# 08_-_PERIPHERALS_A.net
KiCad netlist of a schematic drawn in Altium Designer
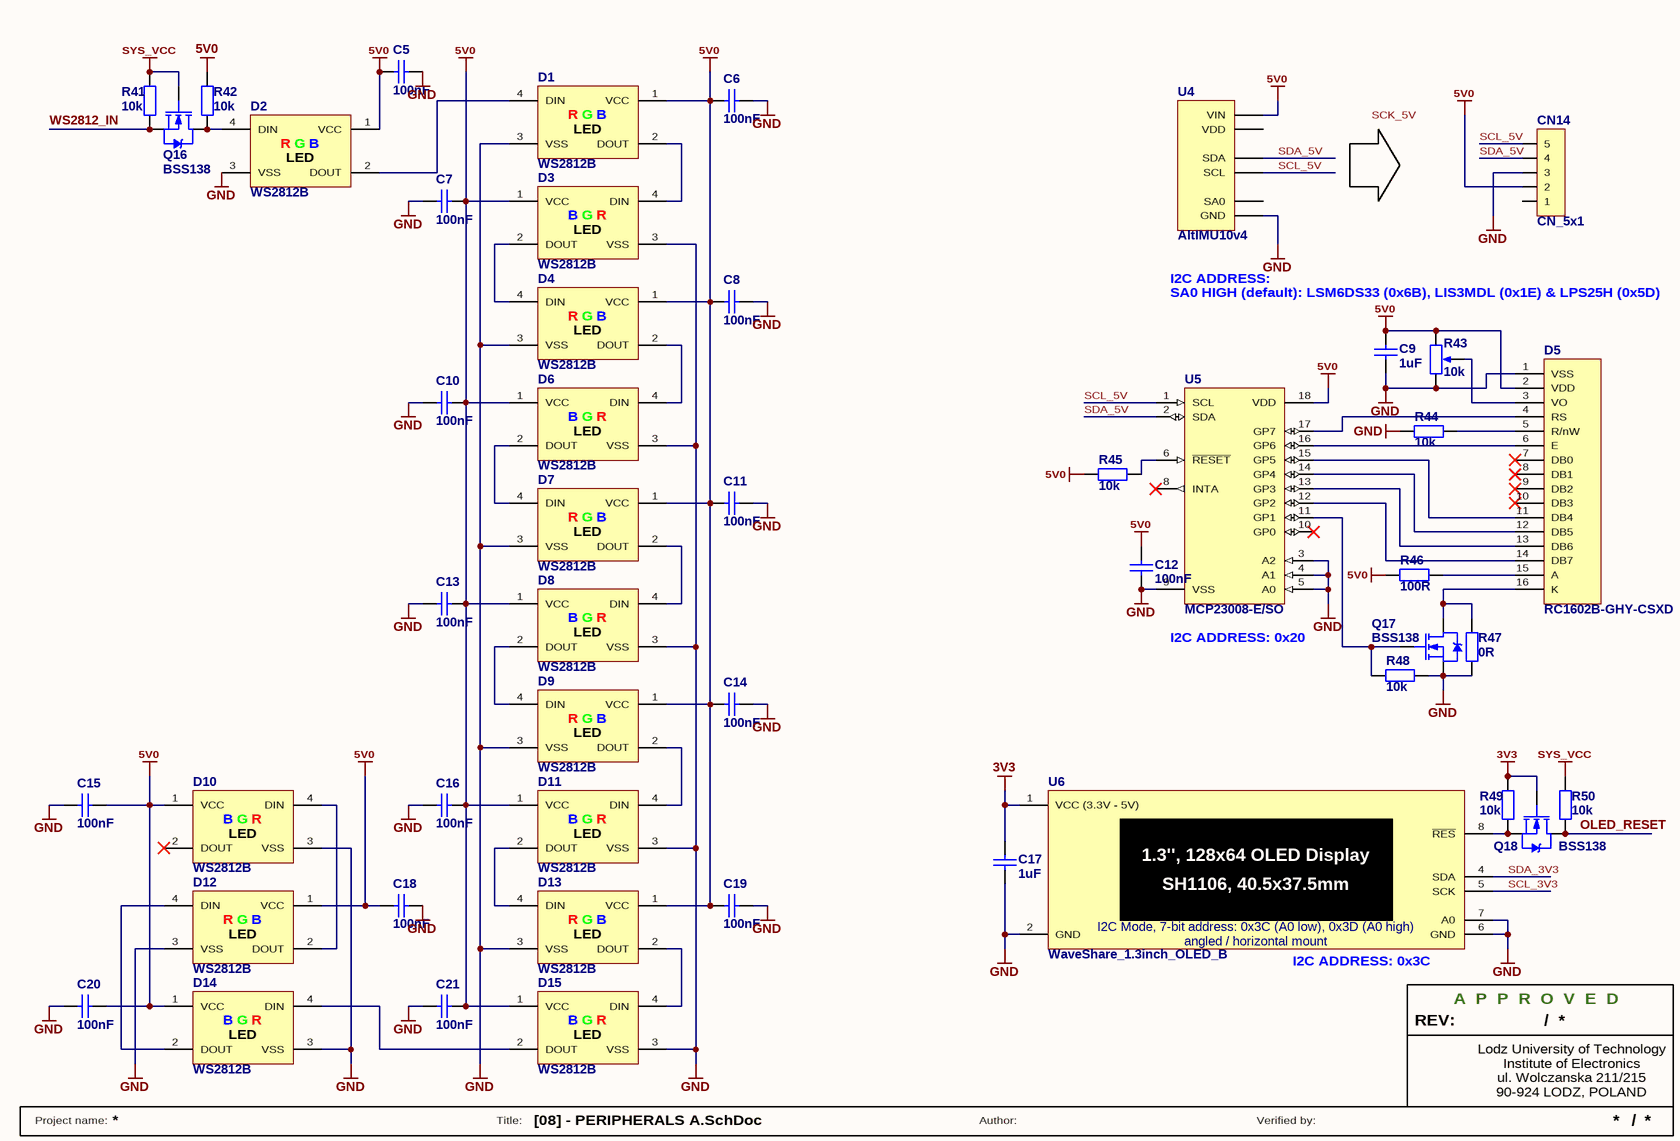
[diagram p0: [08] - PERIPHERALS A.SchDoc]

(export (version "E")
  (design (tool "Eeschema 10.0.6"))
  (components
    (comp (ref "C5")
      (value "100nF")
      (footprint "C0805")
      (description "Capacitor")
      (libsource (lib "capacitors") (part "Cap"))
    )
    (comp (ref "C6")
      (value "100nF")
      (footprint "C0805")
      (description "Capacitor")
      (libsource (lib "capacitors") (part "Cap"))
    )
    (comp (ref "C7")
      (value "100nF")
      (footprint "C0805")
      (description "Capacitor")
      (libsource (lib "capacitors") (part "Cap"))
    )
    (comp (ref "C8")
      (value "100nF")
      (footprint "C0805")
      (description "Capacitor")
      (libsource (lib "capacitors") (part "Cap"))
    )
    (comp (ref "C9")
      (value "1uF")
      (footprint "C0805")
      (description "Capacitor")
      (libsource (lib "capacitors") (part "Cap"))
    )
    (comp (ref "C10")
      (value "100nF")
      (footprint "C0805")
      (description "Capacitor")
      (libsource (lib "capacitors") (part "Cap"))
    )
    (comp (ref "C11")
      (value "100nF")
      (footprint "C0805")
      (description "Capacitor")
      (libsource (lib "capacitors") (part "Cap"))
    )
    (comp (ref "C12")
      (value "100nF")
      (footprint "C0805")
      (description "Capacitor")
      (libsource (lib "capacitors") (part "Cap"))
    )
    (comp (ref "C13")
      (value "100nF")
      (footprint "C0805")
      (description "Capacitor")
      (libsource (lib "capacitors") (part "Cap"))
    )
    (comp (ref "C14")
      (value "100nF")
      (footprint "C0805")
      (description "Capacitor")
      (libsource (lib "capacitors") (part "Cap"))
    )
    (comp (ref "C15")
      (value "100nF")
      (footprint "C0805")
      (description "Capacitor")
      (libsource (lib "capacitors") (part "Cap"))
    )
    (comp (ref "C16")
      (value "100nF")
      (footprint "C0805")
      (description "Capacitor")
      (libsource (lib "capacitors") (part "Cap"))
    )
    (comp (ref "C17")
      (value "1uF")
      (footprint "C0805")
      (description "Capacitor")
      (libsource (lib "capacitors") (part "Cap"))
    )
    (comp (ref "C18")
      (value "100nF")
      (footprint "C0805")
      (description "Capacitor")
      (libsource (lib "capacitors") (part "Cap"))
    )
    (comp (ref "C19")
      (value "100nF")
      (footprint "C0805")
      (description "Capacitor")
      (libsource (lib "capacitors") (part "Cap"))
    )
    (comp (ref "C20")
      (value "100nF")
      (footprint "C0805")
      (description "Capacitor")
      (libsource (lib "capacitors") (part "Cap"))
    )
    (comp (ref "C21")
      (value "100nF")
      (footprint "C0805")
      (description "Capacitor")
      (libsource (lib "capacitors") (part "Cap"))
    )
    (comp (ref "CN14")
      (value "CN_5x1")
      (footprint "GP_5x1H_F")
      (libsource (lib "goldpin_female") (part "CN_5x1"))
    )
    (comp (ref "D1")
      (value "WS2812B")
      (footprint "WS2812B")
      (description "Intelligent control LED integrated light source")
      (libsource (lib "") (part "WS2812B_1"))
    )
    (comp (ref "D2")
      (value "WS2812B")
      (footprint "WS2812B")
      (description "Intelligent control LED integrated light source")
      (libsource (lib "") (part "WS2812B_1"))
    )
    (comp (ref "D3")
      (value "WS2812B")
      (footprint "WS2812B")
      (description "Intelligent control LED integrated light source")
      (libsource (lib "leds") (part "WS2812B"))
    )
    (comp (ref "D4")
      (value "WS2812B")
      (footprint "WS2812B")
      (description "Intelligent control LED integrated light source")
      (libsource (lib "") (part "WS2812B_1"))
    )
    (comp (ref "D5")
      (value "RC1602B-GHY-CSXD")
      (footprint "RC1602B-GHY-CSXD")
      (description "16x2 LCD Display")
      (libsource (lib "lcd_displays") (part "RC1602B-GHY-CSXD"))
    )
    (comp (ref "D6")
      (value "WS2812B")
      (footprint "WS2812B")
      (description "Intelligent control LED integrated light source")
      (libsource (lib "leds") (part "WS2812B"))
    )
    (comp (ref "D7")
      (value "WS2812B")
      (footprint "WS2812B")
      (description "Intelligent control LED integrated light source")
      (libsource (lib "") (part "WS2812B_1"))
    )
    (comp (ref "D8")
      (value "WS2812B")
      (footprint "WS2812B")
      (description "Intelligent control LED integrated light source")
      (libsource (lib "leds") (part "WS2812B"))
    )
    (comp (ref "D9")
      (value "WS2812B")
      (footprint "WS2812B")
      (description "Intelligent control LED integrated light source")
      (libsource (lib "") (part "WS2812B_1"))
    )
    (comp (ref "D10")
      (value "WS2812B")
      (footprint "WS2812B")
      (description "Intelligent control LED integrated light source")
      (libsource (lib "leds") (part "WS2812B"))
    )
    (comp (ref "D11")
      (value "WS2812B")
      (footprint "WS2812B")
      (description "Intelligent control LED integrated light source")
      (libsource (lib "leds") (part "WS2812B"))
    )
    (comp (ref "D12")
      (value "WS2812B")
      (footprint "WS2812B")
      (description "Intelligent control LED integrated light source")
      (libsource (lib "") (part "WS2812B_1"))
    )
    (comp (ref "D13")
      (value "WS2812B")
      (footprint "WS2812B")
      (description "Intelligent control LED integrated light source")
      (libsource (lib "") (part "WS2812B_1"))
    )
    (comp (ref "D14")
      (value "WS2812B")
      (footprint "WS2812B")
      (description "Intelligent control LED integrated light source")
      (libsource (lib "leds") (part "WS2812B"))
    )
    (comp (ref "D15")
      (value "WS2812B")
      (footprint "WS2812B")
      (description "Intelligent control LED integrated light source")
      (libsource (lib "leds") (part "WS2812B"))
    )
    (comp (ref "Q16")
      (value "BSS138")
      (footprint "SOT-23")
      (description "N-Channel Enhancement Mode Vertical DMOS FET")
      (fields (field (name "PUBLISHER") "Altium Limited"))
      (libsource (lib "transistors_other") (part "BSS138"))
    )
    (comp (ref "Q17")
      (value "BSS138")
      (footprint "SOT-23")
      (description "N-Channel Enhancement Mode Vertical DMOS FET")
      (fields (field (name "PUBLISHER") "Altium Limited"))
      (libsource (lib "transistors_other") (part "BSS138"))
    )
    (comp (ref "Q18")
      (value "BSS138")
      (footprint "SOT-23")
      (description "N-Channel Enhancement Mode Vertical DMOS FET")
      (fields (field (name "PUBLISHER") "Altium Limited"))
      (libsource (lib "transistors_other") (part "BSS138"))
    )
    (comp (ref "R41")
      (value "10k")
      (footprint "R0805")
      (description "Resistor")
      (libsource (lib "") (part "Res_1"))
    )
    (comp (ref "R42")
      (value "10k")
      (footprint "R0805")
      (description "Resistor")
      (libsource (lib "") (part "Res_1"))
    )
    (comp (ref "R43")
      (value "10k")
      (footprint "3305SMD")
      (description "3305SMD-10K")
      (libsource (lib "resistors") (part "3305SMD-10K"))
    )
    (comp (ref "R44")
      (value "10k")
      (footprint "R0805")
      (description "Resistor")
      (libsource (lib "resistors") (part "Res"))
    )
    (comp (ref "R45")
      (value "10k")
      (footprint "R0805")
      (description "Resistor")
      (libsource (lib "resistors") (part "Res"))
    )
    (comp (ref "R46")
      (value "100R")
      (footprint "R0805")
      (description "Resistor")
      (libsource (lib "resistors") (part "Res"))
    )
    (comp (ref "R47")
      (value "0R")
      (footprint "R0805")
      (description "Resistor")
      (libsource (lib "") (part "Res_2"))
    )
    (comp (ref "R48")
      (value "10k")
      (footprint "R0805")
      (description "Resistor")
      (libsource (lib "resistors") (part "Res"))
    )
    (comp (ref "R49")
      (value "10k")
      (footprint "R0805")
      (description "Resistor")
      (libsource (lib "") (part "Res_1"))
    )
    (comp (ref "R50")
      (value "10k")
      (footprint "R0805")
      (description "Resistor")
      (libsource (lib "") (part "Res_1"))
    )
    (comp (ref "U4")
      (value "AltIMU10v4")
      (footprint "AltIMU-10 v4_REVERSE")
      (description "Pololu Gyro, Accelerometer, Compass, and Altimeter (L3GD20H, LSM303D, and LPS25H Carrier)")
      (libsource (lib "mems_and_imu_modules") (part "AltIMU10v4"))
    )
    (comp (ref "U5")
      (value "MCP23008-E/SO")
      (footprint "SO18W")
      (description "8-Bit I/O Expander with Serial Interface I2C, 18-Pin SOIC Package")
      (libsource (lib "io_expanders") (part "MCP23008-E/SO"))
    )
    (comp (ref "U6")
      (value "WaveShare_1.3inch_OLED_B")
      (footprint "WaveShare_1.3INCH_OLED")
      (description "DEP096032B-W OLED Display")
      (libsource (lib "oled_displays") (part "WaveShare_1.3inch_OLED"))
    )
  )
  (nets
    (net (code "1") (name "/OLED_RESET") (class "Default")
      (node (ref "Q18") (pin "3") (pinfunction "D_3") (pintype "passive"))
      (node (ref "R50") (pin "1") (pinfunction "1_1") (pintype "passive"))
    )
    (net (code "3") (name "/SCL_3V3") (class "Default")
      (node (ref "U6") (pin "5") (pinfunction "SCK_5") (pintype "passive"))
    )
    (net (code "4") (name "/SCL_5V") (class "Default")
      (node (ref "CN14") (pin "5") (pinfunction "5_5") (pintype "passive"))
      (node (ref "U4") (pin "6") (pinfunction "SCL_6") (pintype "passive"))
      (node (ref "U5") (pin "1") (pinfunction "SCL_1") (pintype "input"))
    )
    (net (code "5") (name "/SDA_3V3") (class "Default")
      (node (ref "U6") (pin "4") (pinfunction "SDA_4") (pintype "passive"))
    )
    (net (code "6") (name "/SDA_5V") (class "Default")
      (node (ref "CN14") (pin "4") (pinfunction "4_4") (pintype "passive"))
      (node (ref "U4") (pin "5") (pinfunction "SDA_5") (pintype "passive"))
      (node (ref "U5") (pin "2") (pinfunction "SDA_2") (pintype "bidirectional"))
    )
    (net (code "7") (name "/WS2812_IN") (class "Default")
      (node (ref "Q16") (pin "2") (pinfunction "S_2") (pintype "passive"))
      (node (ref "R41") (pin "1") (pinfunction "1_1") (pintype "passive"))
    )
    (net (code "8") (name "3V3") (class "Default")
      (node (ref "C17") (pin "2") (pinfunction "2_2") (pintype "passive"))
      (node (ref "Q18") (pin "1") (pinfunction "G_1") (pintype "passive"))
      (node (ref "R49") (pin "2") (pinfunction "2_2") (pintype "passive"))
      (node (ref "U6") (pin "1") (pinfunction "VCC_(3.3V_-_5V)_1") (pintype "passive"))
    )
    (net (code "9") (name "5V0") (class "Default")
      (node (ref "C10") (pin "2") (pinfunction "2_2") (pintype "passive"))
      (node (ref "C11") (pin "1") (pinfunction "1_1") (pintype "passive"))
      (node (ref "C12") (pin "2") (pinfunction "2_2") (pintype "passive"))
      (node (ref "C13") (pin "2") (pinfunction "2_2") (pintype "passive"))
      (node (ref "C14") (pin "1") (pinfunction "1_1") (pintype "passive"))
      (node (ref "C15") (pin "2") (pinfunction "2_2") (pintype "passive"))
      (node (ref "C16") (pin "2") (pinfunction "2_2") (pintype "passive"))
      (node (ref "C18") (pin "1") (pinfunction "1_1") (pintype "passive"))
      (node (ref "C19") (pin "1") (pinfunction "1_1") (pintype "passive"))
      (node (ref "C20") (pin "2") (pinfunction "2_2") (pintype "passive"))
      (node (ref "C21") (pin "2") (pinfunction "2_2") (pintype "passive"))
      (node (ref "C5") (pin "1") (pinfunction "1_1") (pintype "passive"))
      (node (ref "C6") (pin "1") (pinfunction "1_1") (pintype "passive"))
      (node (ref "C7") (pin "2") (pinfunction "2_2") (pintype "passive"))
      (node (ref "C8") (pin "1") (pinfunction "1_1") (pintype "passive"))
      (node (ref "C9") (pin "2") (pinfunction "2_2") (pintype "passive"))
      (node (ref "CN14") (pin "2") (pinfunction "2_2") (pintype "passive"))
      (node (ref "D1") (pin "1") (pinfunction "VCC_1") (pintype "power_in"))
      (node (ref "D10") (pin "1") (pinfunction "VCC_1") (pintype "power_in"))
      (node (ref "D11") (pin "1") (pinfunction "VCC_1") (pintype "power_in"))
      (node (ref "D12") (pin "1") (pinfunction "VCC_1") (pintype "power_in"))
      (node (ref "D13") (pin "1") (pinfunction "VCC_1") (pintype "power_in"))
      (node (ref "D14") (pin "1") (pinfunction "VCC_1") (pintype "power_in"))
      (node (ref "D15") (pin "1") (pinfunction "VCC_1") (pintype "power_in"))
      (node (ref "D2") (pin "1") (pinfunction "VCC_1") (pintype "power_in"))
      (node (ref "D3") (pin "1") (pinfunction "VCC_1") (pintype "power_in"))
      (node (ref "D4") (pin "1") (pinfunction "VCC_1") (pintype "power_in"))
      (node (ref "D5") (pin "2") (pinfunction "VDD_2") (pintype "power_in"))
      (node (ref "D6") (pin "1") (pinfunction "VCC_1") (pintype "power_in"))
      (node (ref "D7") (pin "1") (pinfunction "VCC_1") (pintype "power_in"))
      (node (ref "D8") (pin "1") (pinfunction "VCC_1") (pintype "power_in"))
      (node (ref "D9") (pin "1") (pinfunction "VCC_1") (pintype "power_in"))
      (node (ref "R42") (pin "2") (pinfunction "2_2") (pintype "passive"))
      (node (ref "R43") (pin "1") (pinfunction "TOP_1") (pintype "passive"))
      (node (ref "R45") (pin "1") (pinfunction "1_1") (pintype "passive"))
      (node (ref "R46") (pin "1") (pinfunction "1_1") (pintype "passive"))
      (node (ref "U4") (pin "3") (pinfunction "VIN_3") (pintype "passive"))
      (node (ref "U5") (pin "18") (pinfunction "VDD_18") (pintype "power_in"))
    )
    (net (code "10") (name "GND") (class "Default")
      (node (ref "C10") (pin "1") (pinfunction "1_1") (pintype "passive"))
      (node (ref "C11") (pin "2") (pinfunction "2_2") (pintype "passive"))
      (node (ref "C12") (pin "1") (pinfunction "1_1") (pintype "passive"))
      (node (ref "C13") (pin "1") (pinfunction "1_1") (pintype "passive"))
      (node (ref "C14") (pin "2") (pinfunction "2_2") (pintype "passive"))
      (node (ref "C15") (pin "1") (pinfunction "1_1") (pintype "passive"))
      (node (ref "C16") (pin "1") (pinfunction "1_1") (pintype "passive"))
      (node (ref "C17") (pin "1") (pinfunction "1_1") (pintype "passive"))
      (node (ref "C18") (pin "2") (pinfunction "2_2") (pintype "passive"))
      (node (ref "C19") (pin "2") (pinfunction "2_2") (pintype "passive"))
      (node (ref "C20") (pin "1") (pinfunction "1_1") (pintype "passive"))
      (node (ref "C21") (pin "1") (pinfunction "1_1") (pintype "passive"))
      (node (ref "C5") (pin "2") (pinfunction "2_2") (pintype "passive"))
      (node (ref "C6") (pin "2") (pinfunction "2_2") (pintype "passive"))
      (node (ref "C7") (pin "1") (pinfunction "1_1") (pintype "passive"))
      (node (ref "C8") (pin "2") (pinfunction "2_2") (pintype "passive"))
      (node (ref "C9") (pin "1") (pinfunction "1_1") (pintype "passive"))
      (node (ref "CN14") (pin "3") (pinfunction "3_3") (pintype "passive"))
      (node (ref "D1") (pin "3") (pinfunction "VSS_3") (pintype "power_in"))
      (node (ref "D10") (pin "3") (pinfunction "VSS_3") (pintype "power_in"))
      (node (ref "D11") (pin "3") (pinfunction "VSS_3") (pintype "power_in"))
      (node (ref "D12") (pin "3") (pinfunction "VSS_3") (pintype "power_in"))
      (node (ref "D13") (pin "3") (pinfunction "VSS_3") (pintype "power_in"))
      (node (ref "D14") (pin "3") (pinfunction "VSS_3") (pintype "power_in"))
      (node (ref "D15") (pin "3") (pinfunction "VSS_3") (pintype "power_in"))
      (node (ref "D2") (pin "3") (pinfunction "VSS_3") (pintype "power_in"))
      (node (ref "D3") (pin "3") (pinfunction "VSS_3") (pintype "power_in"))
      (node (ref "D4") (pin "3") (pinfunction "VSS_3") (pintype "power_in"))
      (node (ref "D5") (pin "1") (pinfunction "VSS_1") (pintype "power_in"))
      (node (ref "D6") (pin "3") (pinfunction "VSS_3") (pintype "power_in"))
      (node (ref "D7") (pin "3") (pinfunction "VSS_3") (pintype "power_in"))
      (node (ref "D8") (pin "3") (pinfunction "VSS_3") (pintype "power_in"))
      (node (ref "D9") (pin "3") (pinfunction "VSS_3") (pintype "power_in"))
      (node (ref "Q17") (pin "2") (pinfunction "S_2") (pintype "passive"))
      (node (ref "R43") (pin "2") (pinfunction "BOT_2") (pintype "passive"))
      (node (ref "R44") (pin "1") (pinfunction "1_1") (pintype "passive"))
      (node (ref "R47") (pin "2") (pinfunction "2_2") (pintype "passive"))
      (node (ref "R48") (pin "2") (pinfunction "2_2") (pintype "passive"))
      (node (ref "U4") (pin "1") (pinfunction "GND_1") (pintype "passive"))
      (node (ref "U5") (pin "3") (pinfunction "A2_3") (pintype "input"))
      (node (ref "U5") (pin "4") (pinfunction "A1_4") (pintype "input"))
      (node (ref "U5") (pin "5") (pinfunction "A0_5") (pintype "input"))
      (node (ref "U5") (pin "9") (pinfunction "VSS_9") (pintype "power_in"))
      (node (ref "U6") (pin "2") (pinfunction "GND_2") (pintype "passive"))
      (node (ref "U6") (pin "6") (pinfunction "GND_6") (pintype "passive"))
      (node (ref "U6") (pin "7") (pinfunction "A0_7") (pintype "passive"))
    )
    (net (code "11") (name "Net-(D1-DIN)") (class "Default")
      (node (ref "D1") (pin "4") (pinfunction "DIN_4") (pintype "power_in"))
      (node (ref "D2") (pin "2") (pinfunction "DOUT_2") (pintype "power_in"))
    )
    (net (code "12") (name "Net-(D1-DOUT)") (class "Default")
      (node (ref "D1") (pin "2") (pinfunction "DOUT_2") (pintype "power_in"))
      (node (ref "D3") (pin "4") (pinfunction "DIN_4") (pintype "power_in"))
    )
    (net (code "13") (name "Net-(D2-DIN)") (class "Default")
      (node (ref "D2") (pin "4") (pinfunction "DIN_4") (pintype "power_in"))
      (node (ref "Q16") (pin "3") (pinfunction "D_3") (pintype "passive"))
      (node (ref "R42") (pin "1") (pinfunction "1_1") (pintype "passive"))
    )
    (net (code "14") (name "Net-(D3-DOUT)") (class "Default")
      (node (ref "D3") (pin "2") (pinfunction "DOUT_2") (pintype "power_in"))
      (node (ref "D4") (pin "4") (pinfunction "DIN_4") (pintype "power_in"))
    )
    (net (code "15") (name "Net-(D4-DOUT)") (class "Default")
      (node (ref "D4") (pin "2") (pinfunction "DOUT_2") (pintype "power_in"))
      (node (ref "D6") (pin "4") (pinfunction "DIN_4") (pintype "power_in"))
    )
    (net (code "16") (name "Net-(D5-A)") (class "Default")
      (node (ref "D5") (pin "15") (pinfunction "A_15") (pintype "power_in"))
      (node (ref "R46") (pin "2") (pinfunction "2_2") (pintype "passive"))
    )
    (net (code "17") (name "Net-(D5-DB4)") (class "Default")
      (node (ref "D5") (pin "11") (pinfunction "DB4_11") (pintype "power_in"))
      (node (ref "U5") (pin "15") (pinfunction "GP5_15") (pintype "bidirectional"))
    )
    (net (code "18") (name "Net-(D5-DB5)") (class "Default")
      (node (ref "D5") (pin "12") (pinfunction "DB5_12") (pintype "power_in"))
      (node (ref "U5") (pin "14") (pinfunction "GP4_14") (pintype "bidirectional"))
    )
    (net (code "19") (name "Net-(D5-DB6)") (class "Default")
      (node (ref "D5") (pin "13") (pinfunction "DB6_13") (pintype "power_in"))
      (node (ref "U5") (pin "13") (pinfunction "GP3_13") (pintype "bidirectional"))
    )
    (net (code "20") (name "Net-(D5-DB7)") (class "Default")
      (node (ref "D5") (pin "14") (pinfunction "DB7_14") (pintype "power_in"))
      (node (ref "U5") (pin "12") (pinfunction "GP2_12") (pintype "bidirectional"))
    )
    (net (code "21") (name "Net-(D5-E)") (class "Default")
      (node (ref "D5") (pin "6") (pinfunction "E_6") (pintype "power_in"))
      (node (ref "U5") (pin "16") (pinfunction "GP6_16") (pintype "bidirectional"))
    )
    (net (code "22") (name "Net-(D5-K)") (class "Default")
      (node (ref "D5") (pin "16") (pinfunction "K_16") (pintype "power_in"))
      (node (ref "Q17") (pin "3") (pinfunction "D_3") (pintype "passive"))
      (node (ref "R47") (pin "1") (pinfunction "1_1") (pintype "passive"))
    )
    (net (code "23") (name "Net-(D5-RS)") (class "Default")
      (node (ref "D5") (pin "4") (pinfunction "RS_4") (pintype "power_in"))
      (node (ref "U5") (pin "17") (pinfunction "GP7_17") (pintype "bidirectional"))
    )
    (net (code "24") (name "Net-(D5-R{slash}nW)") (class "Default")
      (node (ref "D5") (pin "5") (pinfunction "R/nW_5") (pintype "power_in"))
      (node (ref "R44") (pin "2") (pinfunction "2_2") (pintype "passive"))
    )
    (net (code "25") (name "Net-(D5-VO)") (class "Default")
      (node (ref "D5") (pin "3") (pinfunction "VO_3") (pintype "power_in"))
      (node (ref "R43") (pin "3") (pinfunction "TAP_3") (pintype "passive"))
    )
    (net (code "26") (name "Net-(D6-DOUT)") (class "Default")
      (node (ref "D6") (pin "2") (pinfunction "DOUT_2") (pintype "power_in"))
      (node (ref "D7") (pin "4") (pinfunction "DIN_4") (pintype "power_in"))
    )
    (net (code "27") (name "Net-(D7-DOUT)") (class "Default")
      (node (ref "D7") (pin "2") (pinfunction "DOUT_2") (pintype "power_in"))
      (node (ref "D8") (pin "4") (pinfunction "DIN_4") (pintype "power_in"))
    )
    (net (code "28") (name "Net-(D8-DOUT)") (class "Default")
      (node (ref "D8") (pin "2") (pinfunction "DOUT_2") (pintype "power_in"))
      (node (ref "D9") (pin "4") (pinfunction "DIN_4") (pintype "power_in"))
    )
    (net (code "29") (name "Net-(D10-DIN)") (class "Default")
      (node (ref "D10") (pin "4") (pinfunction "DIN_4") (pintype "power_in"))
      (node (ref "D12") (pin "2") (pinfunction "DOUT_2") (pintype "power_in"))
    )
    (net (code "30") (name "Net-(D11-DIN)") (class "Default")
      (node (ref "D11") (pin "4") (pinfunction "DIN_4") (pintype "power_in"))
      (node (ref "D9") (pin "2") (pinfunction "DOUT_2") (pintype "power_in"))
    )
    (net (code "31") (name "Net-(D11-DOUT)") (class "Default")
      (node (ref "D11") (pin "2") (pinfunction "DOUT_2") (pintype "power_in"))
      (node (ref "D13") (pin "4") (pinfunction "DIN_4") (pintype "power_in"))
    )
    (net (code "32") (name "Net-(D12-DIN)") (class "Default")
      (node (ref "D12") (pin "4") (pinfunction "DIN_4") (pintype "power_in"))
      (node (ref "D14") (pin "2") (pinfunction "DOUT_2") (pintype "power_in"))
    )
    (net (code "33") (name "Net-(D13-DOUT)") (class "Default")
      (node (ref "D13") (pin "2") (pinfunction "DOUT_2") (pintype "power_in"))
      (node (ref "D15") (pin "4") (pinfunction "DIN_4") (pintype "power_in"))
    )
    (net (code "34") (name "Net-(D14-DIN)") (class "Default")
      (node (ref "D14") (pin "4") (pinfunction "DIN_4") (pintype "power_in"))
      (node (ref "D15") (pin "2") (pinfunction "DOUT_2") (pintype "power_in"))
    )
    (net (code "35") (name "Net-(Q17-G)") (class "Default")
      (node (ref "Q17") (pin "1") (pinfunction "G_1") (pintype "passive"))
      (node (ref "R48") (pin "1") (pinfunction "1_1") (pintype "passive"))
      (node (ref "U5") (pin "11") (pinfunction "GP1_11") (pintype "bidirectional"))
    )
    (net (code "36") (name "Net-(Q18-S)") (class "Default")
      (node (ref "Q18") (pin "2") (pinfunction "S_2") (pintype "passive"))
      (node (ref "R49") (pin "1") (pinfunction "1_1") (pintype "passive"))
      (node (ref "U6") (pin "8") (pinfunction "~{RES}_8") (pintype "passive"))
    )
    (net (code "37") (name "Net-(U5-~{RESET})") (class "Default")
      (node (ref "R45") (pin "2") (pinfunction "2_2") (pintype "passive"))
      (node (ref "U5") (pin "6") (pinfunction "~{RESET}_6") (pintype "input"))
    )
    (net (code "38") (name "SYS_VCC") (class "Default")
      (node (ref "Q16") (pin "1") (pinfunction "G_1") (pintype "passive"))
      (node (ref "R41") (pin "2") (pinfunction "2_2") (pintype "passive"))
      (node (ref "R50") (pin "2") (pinfunction "2_2") (pintype "passive"))
    )
    (net (code "39") (name "unconnected-(CN14-Pad1)") (class "Default")
      (node (ref "CN14") (pin "1") (pinfunction "1_1") (pintype "passive"))
    )
    (net (code "40") (name "unconnected-(D5-DB0-Pad7)") (class "Default")
      (node (ref "D5") (pin "7") (pinfunction "DB0_7") (pintype "power_in+no_connect"))
    )
    (net (code "41") (name "unconnected-(D5-DB1-Pad8)") (class "Default")
      (node (ref "D5") (pin "8") (pinfunction "DB1_8") (pintype "power_in+no_connect"))
    )
    (net (code "42") (name "unconnected-(D5-DB2-Pad9)") (class "Default")
      (node (ref "D5") (pin "9") (pinfunction "DB2_9") (pintype "power_in+no_connect"))
    )
    (net (code "43") (name "unconnected-(D5-DB3-Pad10)") (class "Default")
      (node (ref "D5") (pin "10") (pinfunction "DB3_10") (pintype "power_in+no_connect"))
    )
    (net (code "44") (name "unconnected-(D10-DOUT-Pad2)") (class "Default")
      (node (ref "D10") (pin "2") (pinfunction "DOUT_2") (pintype "power_in+no_connect"))
    )
    (net (code "45") (name "unconnected-(U4-SA0-Pad2)") (class "Default")
      (node (ref "U4") (pin "2") (pinfunction "SA0_2") (pintype "passive"))
    )
    (net (code "46") (name "unconnected-(U4-VDD-Pad4)") (class "Default")
      (node (ref "U4") (pin "4") (pinfunction "VDD_4") (pintype "passive"))
    )
    (net (code "47") (name "unconnected-(U5-GP0-Pad10)") (class "Default")
      (node (ref "U5") (pin "10") (pinfunction "GP0_10") (pintype "bidirectional+no_connect"))
    )
    (net (code "48") (name "unconnected-(U5-INTA-Pad8)") (class "Default")
      (node (ref "U5") (pin "8") (pinfunction "INTA_8") (pintype "output+no_connect"))
    )
  )
)
